# Adafruit_USB_Power_Gauge.net
KiCad netlist of a schematic drawn in EAGLE
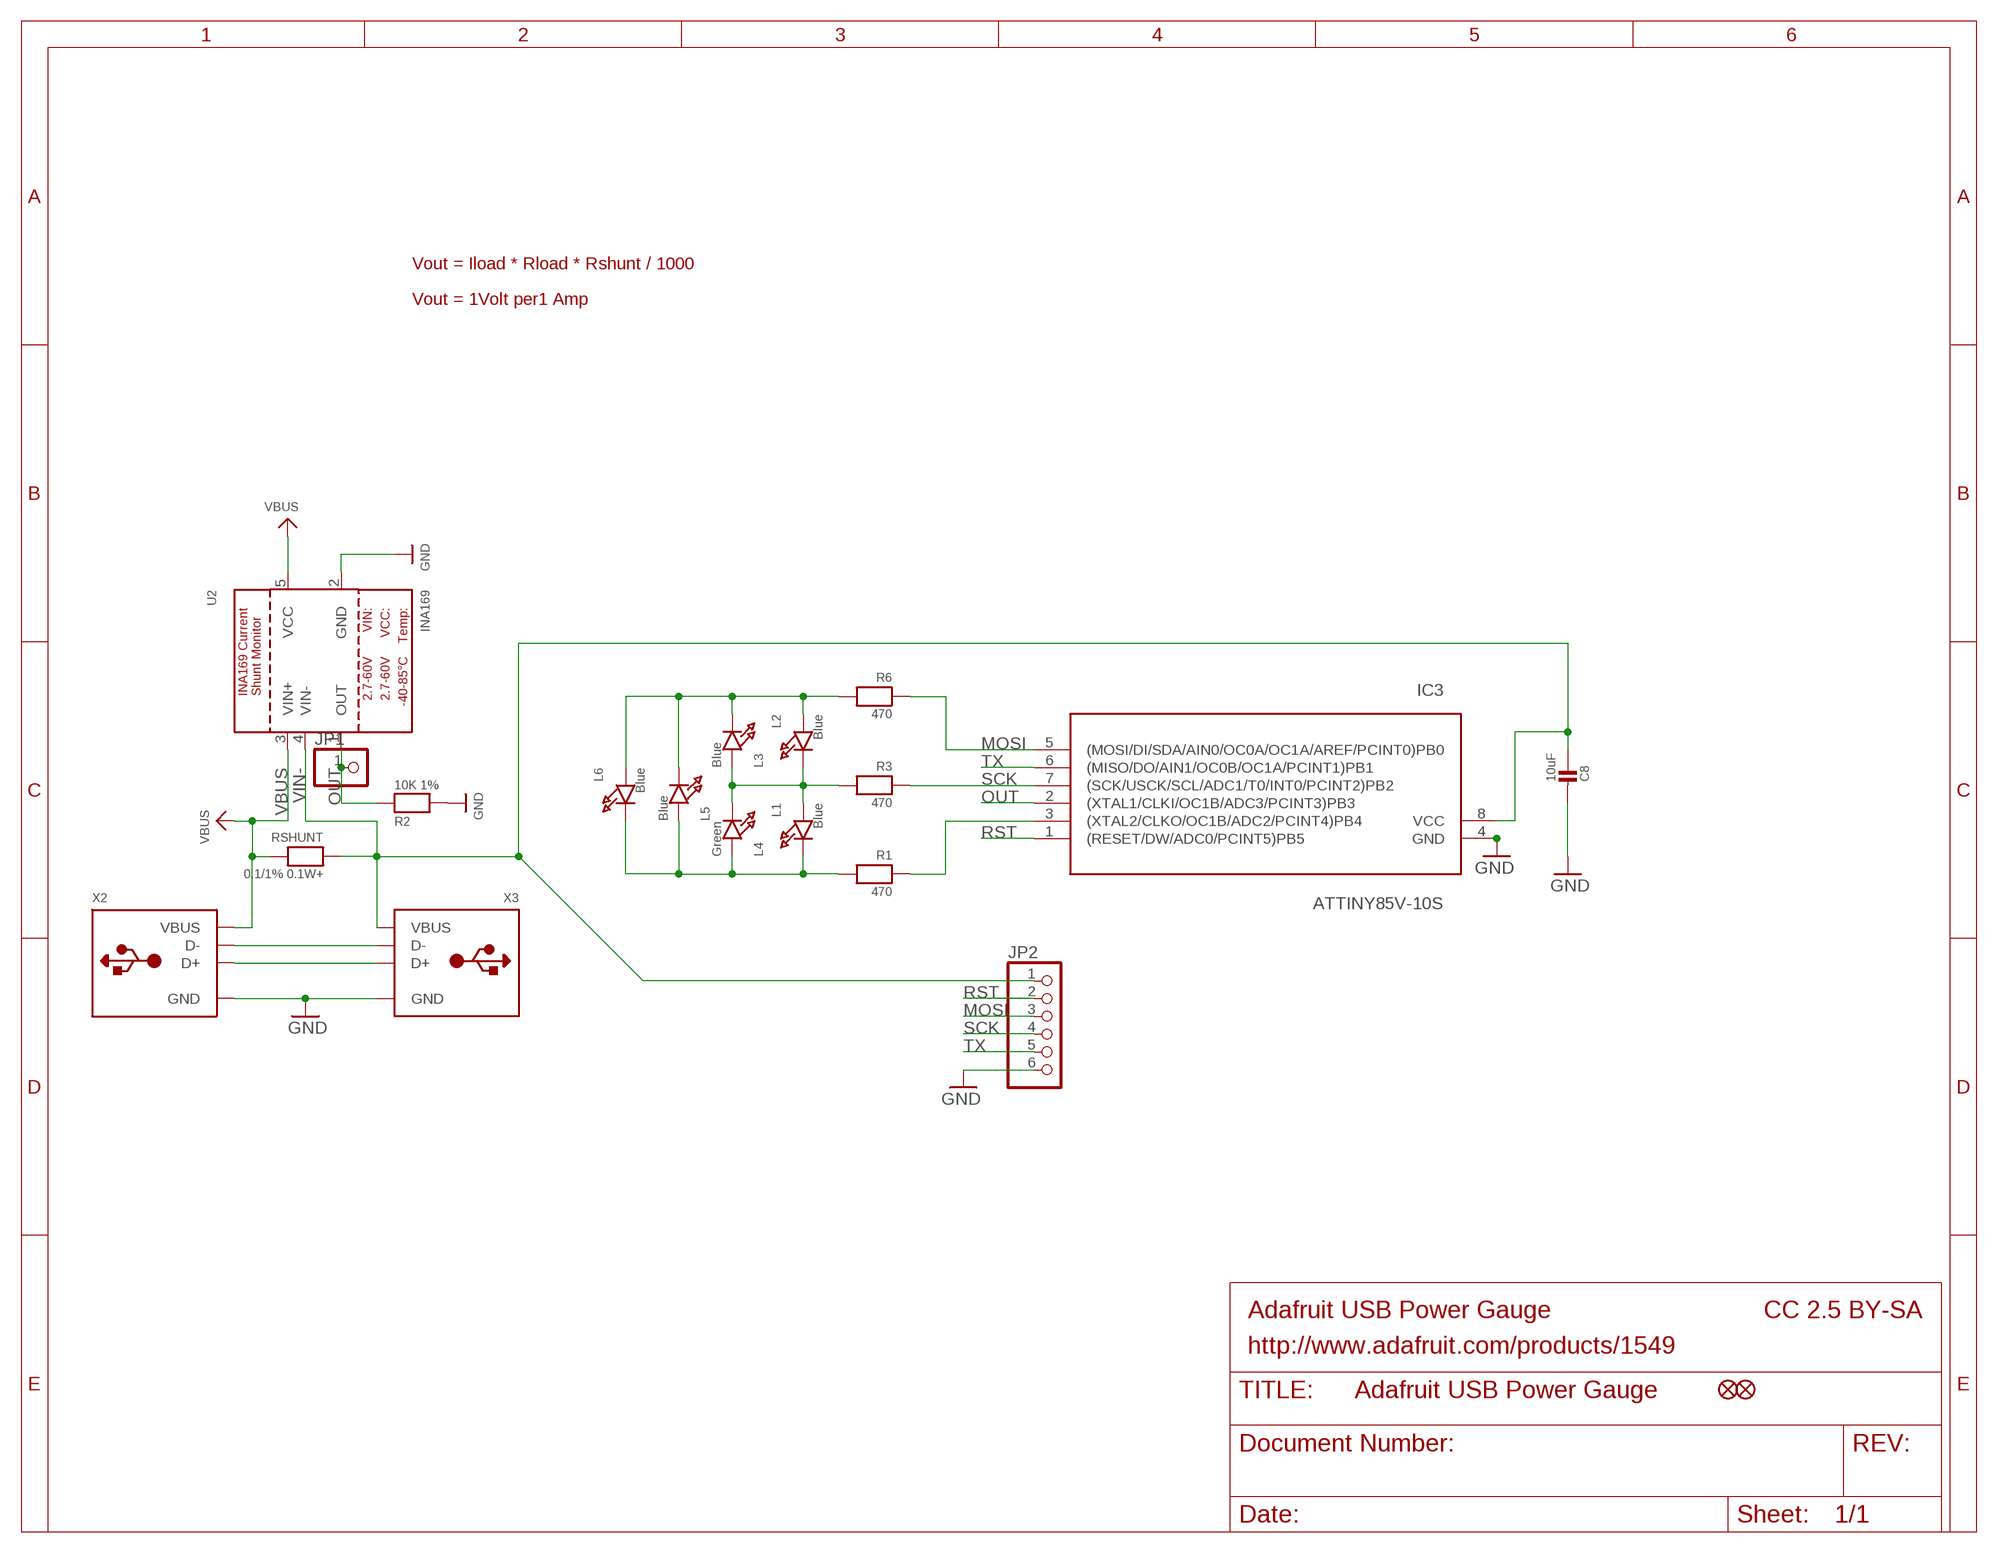
[diagram p0: schematic, sheet 1]

(export (version "E")
  (design (tool "Eeschema 10.0.6"))
  (components
    (comp (ref "C8")
      (value "10uF")
      (footprint "eagle-import:0805-NO")
      (libsource (lib "eagle-import") (part "CAP_CERAMIC0805-NOOUTLINE"))
    )
    (comp (ref "FID1")
      (value "FIDUCIAL\"\"")
      (footprint "eagle-import:FIDUCIAL_1MM")
      (libsource (lib "eagle-import") (part "FIDUCIAL{dblquote}{dblquote}"))
    )
    (comp (ref "FID2")
      (value "FIDUCIAL\"\"")
      (footprint "eagle-import:FIDUCIAL_1MM")
      (libsource (lib "eagle-import") (part "FIDUCIAL{dblquote}{dblquote}"))
    )
    (comp (ref "IC3")
      (value "ATTINY85V-10S")
      (footprint "eagle-import:SOIC8")
      (libsource (lib "eagle-import") (part "ATTINY85SV-10"))
    )
    (comp (ref "JP1")
      (value "PINHD-1X1CB")
      (footprint "eagle-import:1X01-CLEANBIG")
      (libsource (lib "eagle-import") (part "PINHD-1X1CB"))
    )
    (comp (ref "JP2")
      (value "PINHD-1X6CB")
      (footprint "eagle-import:1X06-CLEANBIG")
      (libsource (lib "eagle-import") (part "PINHD-1X6CB"))
    )
    (comp (ref "L1")
      (value "Blue")
      (footprint "eagle-import:CHIPLED_0805_NOOUTLINE")
      (libsource (lib "eagle-import") (part "LED0805_NOOUTLINE"))
    )
    (comp (ref "L2")
      (value "Blue")
      (footprint "eagle-import:CHIPLED_0805_NOOUTLINE")
      (libsource (lib "eagle-import") (part "LED0805_NOOUTLINE"))
    )
    (comp (ref "L3")
      (value "Blue")
      (footprint "eagle-import:CHIPLED_0805_NOOUTLINE")
      (libsource (lib "eagle-import") (part "LED0805_NOOUTLINE"))
    )
    (comp (ref "L4")
      (value "Green")
      (footprint "eagle-import:CHIPLED_0805_NOOUTLINE")
      (libsource (lib "eagle-import") (part "LED0805_NOOUTLINE"))
    )
    (comp (ref "L5")
      (value "Blue")
      (footprint "eagle-import:CHIPLED_0805_NOOUTLINE")
      (libsource (lib "eagle-import") (part "LED0805_NOOUTLINE"))
    )
    (comp (ref "L6")
      (value "Blue")
      (footprint "eagle-import:CHIPLED_0805_NOOUTLINE")
      (libsource (lib "eagle-import") (part "LED0805_NOOUTLINE"))
    )
    (comp (ref "R1")
      (value "470")
      (footprint "eagle-import:0805-NO")
      (libsource (lib "eagle-import") (part "RESISTOR0805_NOOUTLINE"))
    )
    (comp (ref "R2")
      (value "10K 1%")
      (footprint "eagle-import:0805-NO")
      (libsource (lib "eagle-import") (part "RESISTOR0805_NOOUTLINE"))
    )
    (comp (ref "R3")
      (value "470")
      (footprint "eagle-import:0805-NO")
      (libsource (lib "eagle-import") (part "RESISTOR0805_NOOUTLINE"))
    )
    (comp (ref "R6")
      (value "470")
      (footprint "eagle-import:0805-NO")
      (libsource (lib "eagle-import") (part "RESISTOR0805_NOOUTLINE"))
    )
    (comp (ref "RSHUNT")
      (value "0.1/1% 0.1W+")
      (footprint "eagle-import:0805-NO")
      (libsource (lib "eagle-import") (part "RESISTOR0805_NOOUTLINE"))
    )
    (comp (ref "U2")
      (value "INA169")
      (footprint "eagle-import:SOT23-5")
      (libsource (lib "eagle-import") (part "INA169"))
    )
    (comp (ref "X2")
      (value "USB_TYPEA_CLIENTTHM")
      (footprint "eagle-import:USB_A-THM")
      (libsource (lib "eagle-import") (part "USB_TYPEA_CLIENTTHM"))
    )
    (comp (ref "X3")
      (value "USB_TYPEAPTHFML")
      (footprint "eagle-import:USB_HOST-PTH")
      (libsource (lib "eagle-import") (part "USB_TYPEAPTHFML"))
    )
  )
  (nets
    (net (code "1") (name "/MOSI") (class "Default")
      (node (ref "IC3") (pin "5") (pinfunction "(MOSI/DI/SDA/AIN0/OC0A/OC1A/AREF/PCINT0)PB0_5") (pintype "bidirectional"))
      (node (ref "JP2") (pin "3") (pinfunction "3_3") (pintype "passive"))
      (node (ref "R6") (pin "1") (pinfunction "1_1") (pintype "passive"))
    )
    (net (code "2") (name "/OUT") (class "Default")
      (node (ref "IC3") (pin "2") (pinfunction "(XTAL1/CLKI/OC1B/ADC3/PCINT3)PB3_2") (pintype "bidirectional"))
      (node (ref "JP1") (pin "1") (pinfunction "1_1") (pintype "passive"))
      (node (ref "R2") (pin "1") (pinfunction "1_1") (pintype "passive"))
      (node (ref "U2") (pin "1") (pinfunction "OUT_1") (pintype "output"))
    )
    (net (code "3") (name "/RST") (class "Default")
      (node (ref "IC3") (pin "1") (pinfunction "(RESET/DW/ADC0/PCINT5)PB5_1") (pintype "bidirectional"))
      (node (ref "JP2") (pin "2") (pinfunction "2_2") (pintype "passive"))
    )
    (net (code "4") (name "/SCK") (class "Default")
      (node (ref "IC3") (pin "7") (pinfunction "(SCK/USCK/SCL/ADC1/T0/INT0/PCINT2)PB2_7") (pintype "bidirectional"))
      (node (ref "JP2") (pin "4") (pinfunction "4_4") (pintype "passive"))
      (node (ref "R3") (pin "1") (pinfunction "1_1") (pintype "passive"))
    )
    (net (code "5") (name "/TX") (class "Default")
      (node (ref "IC3") (pin "6") (pinfunction "(MISO/DO/AIN1/OC0B/OC1A/PCINT1)PB1_6") (pintype "bidirectional"))
      (node (ref "JP2") (pin "5") (pinfunction "5_5") (pintype "passive"))
    )
    (net (code "6") (name "/VIN-") (class "Default")
      (node (ref "C8") (pin "1") (pinfunction "1_1") (pintype "passive"))
      (node (ref "IC3") (pin "8") (pinfunction "VCC_8") (pintype "bidirectional"))
      (node (ref "JP2") (pin "1") (pinfunction "1_1") (pintype "passive"))
      (node (ref "RSHUNT") (pin "1") (pinfunction "1_1") (pintype "passive"))
      (node (ref "U2") (pin "4") (pinfunction "VIN-_4") (pintype "bidirectional"))
      (node (ref "X3") (pin "VBUS") (pinfunction "VBUS_VBUS") (pintype "power_in"))
    )
    (net (code "7") (name "GND") (class "Default")
      (node (ref "C8") (pin "2") (pinfunction "2_2") (pintype "passive"))
      (node (ref "IC3") (pin "4") (pinfunction "GND_4") (pintype "bidirectional"))
      (node (ref "JP2") (pin "6") (pinfunction "6_6") (pintype "passive"))
      (node (ref "R2") (pin "2") (pinfunction "2_2") (pintype "passive"))
      (node (ref "U2") (pin "2") (pinfunction "GND_2") (pintype "power_in"))
      (node (ref "X2") (pin "GND") (pinfunction "GND_GND") (pintype "power_in"))
      (node (ref "X3") (pin "GND") (pinfunction "GND_GND") (pintype "power_in"))
    )
    (net (code "8") (name "Net-(IC3-(XTAL2{slash}CLKO{slash}OC1B{slash}ADC2{slash}PCINT4)PB4)") (class "Default")
      (node (ref "IC3") (pin "3") (pinfunction "(XTAL2/CLKO/OC1B/ADC2/PCINT4)PB4_3") (pintype "bidirectional"))
      (node (ref "R1") (pin "1") (pinfunction "1_1") (pintype "passive"))
    )
    (net (code "9") (name "Net-(L1-PadA)") (class "Default")
      (node (ref "L1") (pin "A") (pinfunction "A_A") (pintype "passive"))
      (node (ref "L2") (pin "C") (pinfunction "C_C") (pintype "passive"))
      (node (ref "L3") (pin "A") (pinfunction "A_A") (pintype "passive"))
      (node (ref "L4") (pin "C") (pinfunction "C_C") (pintype "passive"))
      (node (ref "R3") (pin "2") (pinfunction "2_2") (pintype "passive"))
    )
    (net (code "10") (name "Net-(L1-PadC)") (class "Default")
      (node (ref "L1") (pin "C") (pinfunction "C_C") (pintype "passive"))
      (node (ref "L4") (pin "A") (pinfunction "A_A") (pintype "passive"))
      (node (ref "L5") (pin "A") (pinfunction "A_A") (pintype "passive"))
      (node (ref "L6") (pin "C") (pinfunction "C_C") (pintype "passive"))
      (node (ref "R1") (pin "2") (pinfunction "2_2") (pintype "passive"))
    )
    (net (code "11") (name "Net-(L2-PadA)") (class "Default")
      (node (ref "L2") (pin "A") (pinfunction "A_A") (pintype "passive"))
      (node (ref "L3") (pin "C") (pinfunction "C_C") (pintype "passive"))
      (node (ref "L5") (pin "C") (pinfunction "C_C") (pintype "passive"))
      (node (ref "L6") (pin "A") (pinfunction "A_A") (pintype "passive"))
      (node (ref "R6") (pin "2") (pinfunction "2_2") (pintype "passive"))
    )
    (net (code "12") (name "Net-(X2-PadD+)") (class "Default")
      (node (ref "X2") (pin "D+") (pinfunction "D+_D+") (pintype "bidirectional"))
      (node (ref "X3") (pin "D+") (pinfunction "D+_D+") (pintype "bidirectional"))
    )
    (net (code "13") (name "Net-(X2-PadD-)") (class "Default")
      (node (ref "X2") (pin "D-") (pinfunction "D-_D-") (pintype "bidirectional"))
      (node (ref "X3") (pin "D-") (pinfunction "D-_D-") (pintype "bidirectional"))
    )
    (net (code "14") (name "VBUS") (class "Default")
      (node (ref "RSHUNT") (pin "2") (pinfunction "2_2") (pintype "passive"))
      (node (ref "U2") (pin "3") (pinfunction "VIN+_3") (pintype "bidirectional"))
      (node (ref "U2") (pin "5") (pinfunction "VCC_5") (pintype "power_in"))
      (node (ref "X2") (pin "VBUS") (pinfunction "VBUS_VBUS") (pintype "power_in"))
    )
  )
)
